# SilentStepStick_v10.net
KiCad netlist of a schematic drawn in EAGLE
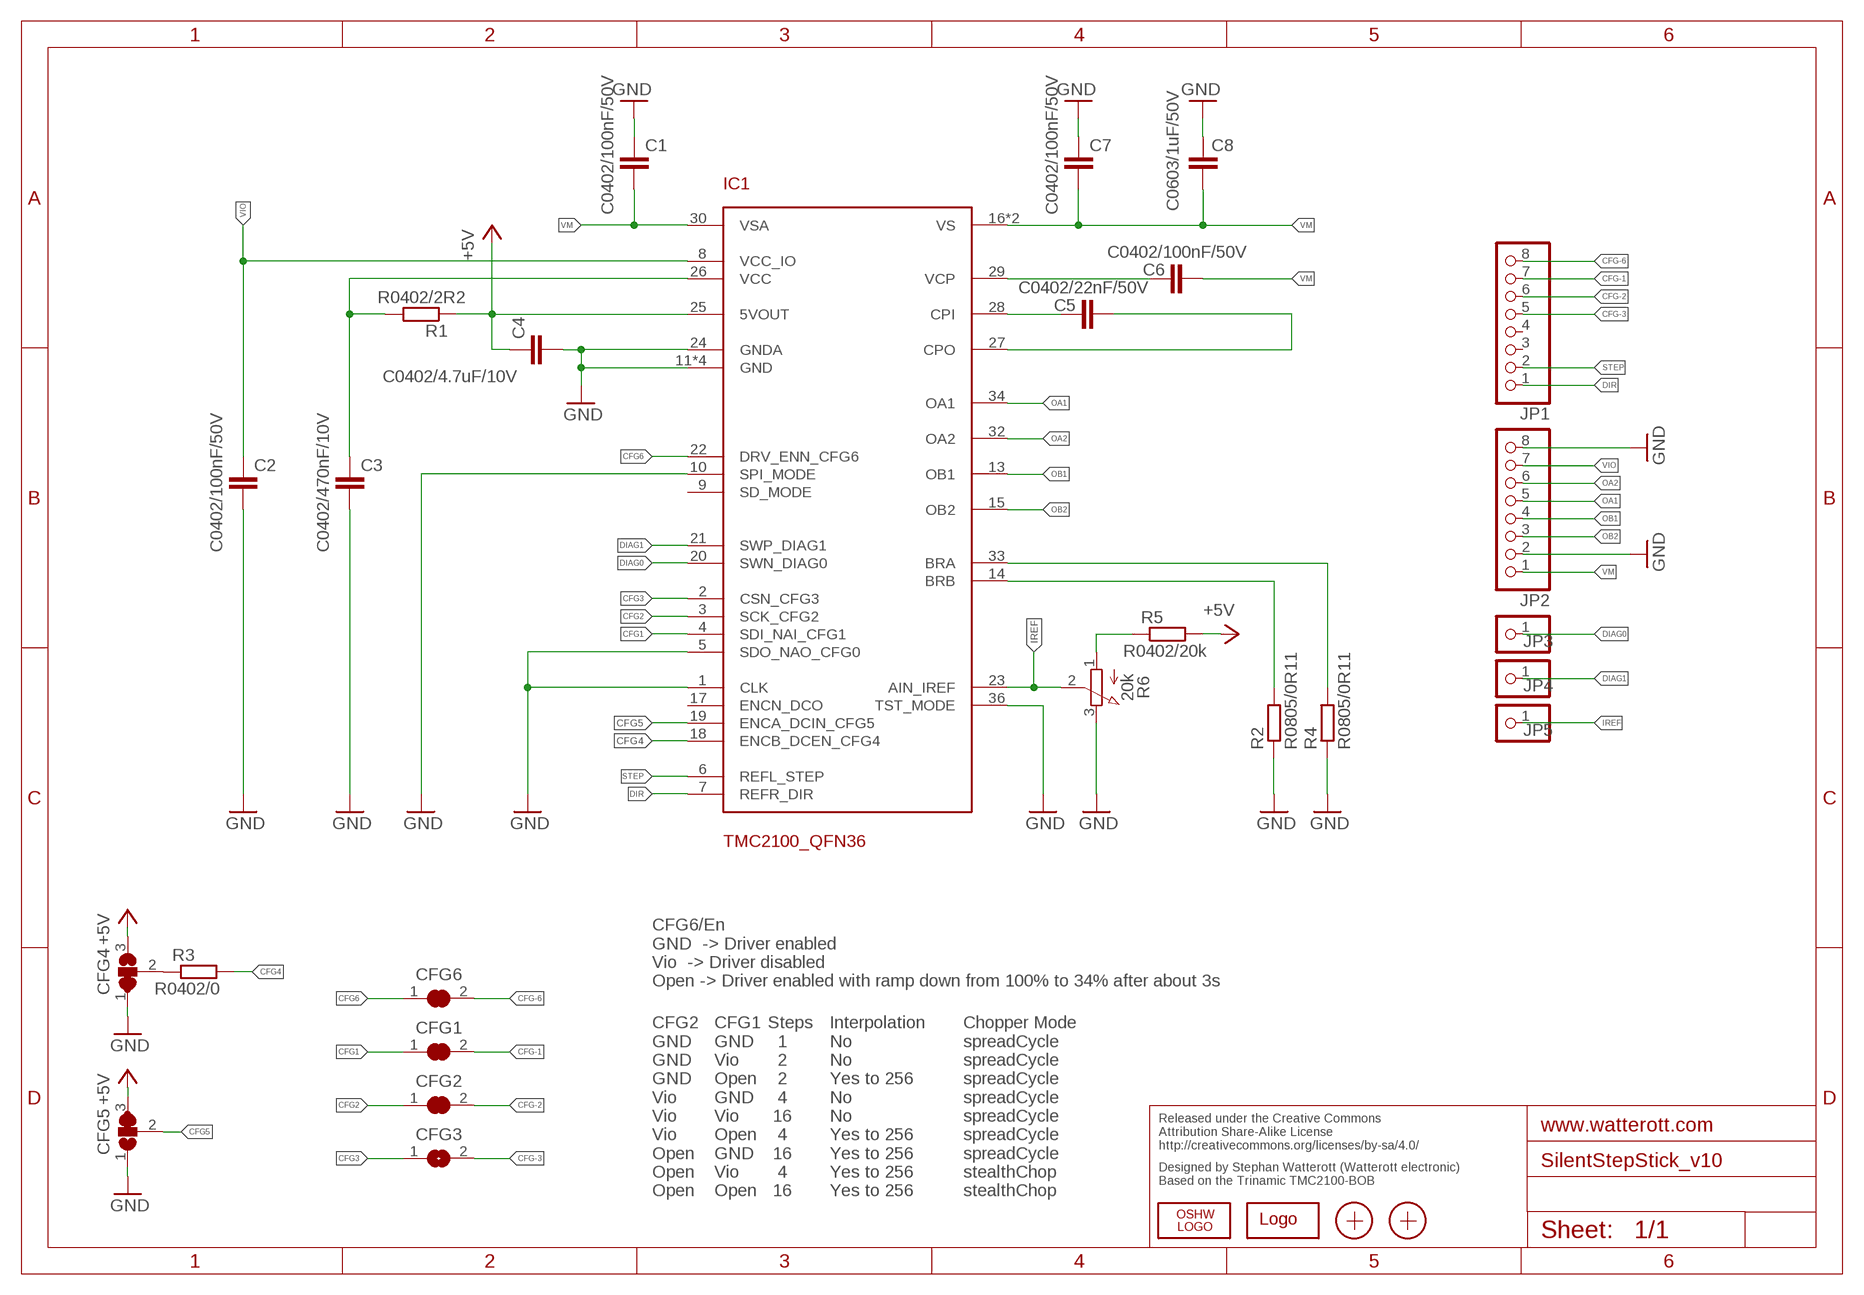
[diagram p0: schematic, sheet 1]

(export (version "E")
  (design (tool "Eeschema 10.0.6"))
  (components
    (comp (ref "C1")
      (value "C0402/100nF/50V")
      (footprint "eagle-import:C0402")
      (libsource (lib "eagle-import") (part "C-EUC0402"))
    )
    (comp (ref "C2")
      (value "C0402/100nF/50V")
      (footprint "eagle-import:C0402")
      (libsource (lib "eagle-import") (part "C-EUC0402"))
    )
    (comp (ref "C3")
      (value "C0402/470nF/10V")
      (footprint "eagle-import:C0402")
      (libsource (lib "eagle-import") (part "C-EUC0402"))
    )
    (comp (ref "C4")
      (value "C0402/4.7uF/10V")
      (footprint "eagle-import:C0402")
      (libsource (lib "eagle-import") (part "C-EUC0402"))
    )
    (comp (ref "C5")
      (value "C0402/22nF/50V")
      (footprint "eagle-import:C0402")
      (libsource (lib "eagle-import") (part "C-EUC0402"))
    )
    (comp (ref "C6")
      (value "C0402/100nF/50V")
      (footprint "eagle-import:C0402")
      (libsource (lib "eagle-import") (part "C-EUC0402"))
    )
    (comp (ref "C7")
      (value "C0402/100nF/50V")
      (footprint "eagle-import:C0402")
      (libsource (lib "eagle-import") (part "C-EUC0402"))
    )
    (comp (ref "C8")
      (value "C0603/1uF/50V")
      (footprint "eagle-import:C0603")
      (libsource (lib "eagle-import") (part "C-EUC0603"))
    )
    (comp (ref "CFG1")
      (value "JUMPER2-0201")
      (footprint "eagle-import:JUMPER2-0201")
      (libsource (lib "eagle-import") (part "JUMPER2-0201"))
    )
    (comp (ref "CFG2")
      (value "JUMPER2-0201")
      (footprint "eagle-import:JUMPER2-0201")
      (libsource (lib "eagle-import") (part "JUMPER2-0201"))
    )
    (comp (ref "CFG3")
      (value "JUMPER2-0201")
      (footprint "eagle-import:JUMPER2-0201")
      (libsource (lib "eagle-import") (part "JUMPER2-0201"))
    )
    (comp (ref "CFG4")
      (value "JUMPER3-0201-NC")
      (footprint "eagle-import:JUMPER3-0201_NC")
      (libsource (lib "eagle-import") (part "JUMPER3-0201-NC"))
    )
    (comp (ref "CFG5")
      (value "JUMPER3-0201")
      (footprint "eagle-import:JUMPER3-0201")
      (libsource (lib "eagle-import") (part "JUMPER3-0201"))
    )
    (comp (ref "CFG6")
      (value "JUMPER2-0201")
      (footprint "eagle-import:JUMPER2-0201")
      (libsource (lib "eagle-import") (part "JUMPER2-0201"))
    )
    (comp (ref "IC1")
      (value "TMC2100_QFN36")
      (footprint "eagle-import:QFN36")
      (libsource (lib "eagle-import") (part "TMC2100_QFN36"))
    )
    (comp (ref "JP1")
      (value "PINHD-1X08_2.54-S")
      (footprint "eagle-import:1X08-S")
      (libsource (lib "eagle-import") (part "PINHD-1X08_2.54-S"))
    )
    (comp (ref "JP2")
      (value "PINHD-1X08_2.54-S")
      (footprint "eagle-import:1X08-S")
      (libsource (lib "eagle-import") (part "PINHD-1X08_2.54-S"))
    )
    (comp (ref "JP3")
      (value "PINHD-1X1")
      (footprint "eagle-import:1X01")
      (libsource (lib "eagle-import") (part "PINHD-1X1"))
    )
    (comp (ref "JP4")
      (value "PINHD-1X1")
      (footprint "eagle-import:1X01")
      (libsource (lib "eagle-import") (part "PINHD-1X1"))
    )
    (comp (ref "JP5")
      (value "PINHD-1X1")
      (footprint "eagle-import:1X01")
      (libsource (lib "eagle-import") (part "PINHD-1X1"))
    )
    (comp (ref "LOGO1")
      (value "OSHW_LOGOX0070")
      (footprint "eagle-import:OSHW_6X70")
      (libsource (lib "eagle-import") (part "OSHW_LOGOX0070"))
    )
    (comp (ref "LOGO2")
      (value "LOGO-S_PLACE_M")
      (footprint "eagle-import:SPARK_TPLACE_M")
      (libsource (lib "eagle-import") (part "LOGO-S_PLACE_M"))
    )
    (comp (ref "R1")
      (value "R0402/2R2")
      (footprint "eagle-import:R0402")
      (libsource (lib "eagle-import") (part "R-EU_R0402"))
    )
    (comp (ref "R2")
      (value "R0805/0R11")
      (footprint "eagle-import:M0805")
      (libsource (lib "eagle-import") (part "R-EU_M0805"))
    )
    (comp (ref "R3")
      (value "R0402/0")
      (footprint "eagle-import:R0402")
      (libsource (lib "eagle-import") (part "R-EU_R0402"))
    )
    (comp (ref "R4")
      (value "R0805/0R11")
      (footprint "eagle-import:M0805")
      (libsource (lib "eagle-import") (part "R-EU_M0805"))
    )
    (comp (ref "R5")
      (value "R0402/20k")
      (footprint "eagle-import:R0402")
      (libsource (lib "eagle-import") (part "R-EU_R0402"))
    )
    (comp (ref "R6")
      (value "20k")
      (footprint "eagle-import:POT_EVM3R")
      (libsource (lib "eagle-import") (part "POTEVM3R"))
    )
    (comp (ref "X1")
      (value "PASSER-07")
      (footprint "eagle-import:PASSER_07MM")
      (libsource (lib "eagle-import") (part "PASSER-07"))
    )
    (comp (ref "X2")
      (value "PASSER-07")
      (footprint "eagle-import:PASSER_07MM")
      (libsource (lib "eagle-import") (part "PASSER-07"))
    )
  )
  (nets
    (net (code "1") (name "+5V") (class "Default")
      (node (ref "C4") (pin "1") (pinfunction "1_1") (pintype "passive"))
      (node (ref "CFG4") (pin "3") (pinfunction "3_3") (pintype "passive"))
      (node (ref "CFG5") (pin "3") (pinfunction "3_3") (pintype "passive"))
      (node (ref "IC1") (pin "25") (pinfunction "5VOUT_25") (pintype "bidirectional"))
      (node (ref "R1") (pin "1") (pinfunction "1_1") (pintype "passive"))
      (node (ref "R5") (pin "2") (pinfunction "2_2") (pintype "passive"))
    )
    (net (code "2") (name "CFG-1") (class "Default")
      (node (ref "CFG1") (pin "2") (pinfunction "2_2") (pintype "passive"))
      (node (ref "JP1") (pin "7") (pinfunction "7_7") (pintype "passive"))
    )
    (net (code "3") (name "CFG-2") (class "Default")
      (node (ref "CFG2") (pin "2") (pinfunction "2_2") (pintype "passive"))
      (node (ref "JP1") (pin "6") (pinfunction "6_6") (pintype "passive"))
    )
    (net (code "4") (name "CFG-3") (class "Default")
      (node (ref "CFG3") (pin "2") (pinfunction "2_2") (pintype "passive"))
      (node (ref "JP1") (pin "5") (pinfunction "5_5") (pintype "passive"))
    )
    (net (code "5") (name "CFG-6") (class "Default")
      (node (ref "CFG6") (pin "2") (pinfunction "2_2") (pintype "passive"))
      (node (ref "JP1") (pin "8") (pinfunction "8_8") (pintype "passive"))
    )
    (net (code "6") (name "CFG1") (class "Default")
      (node (ref "CFG1") (pin "1") (pinfunction "1_1") (pintype "passive"))
      (node (ref "IC1") (pin "4") (pinfunction "SDI_NAI_CFG1_4") (pintype "bidirectional"))
    )
    (net (code "7") (name "CFG2") (class "Default")
      (node (ref "CFG2") (pin "1") (pinfunction "1_1") (pintype "passive"))
      (node (ref "IC1") (pin "3") (pinfunction "SCK_CFG2_3") (pintype "bidirectional"))
    )
    (net (code "8") (name "CFG3") (class "Default")
      (node (ref "CFG3") (pin "1") (pinfunction "1_1") (pintype "passive"))
      (node (ref "IC1") (pin "2") (pinfunction "CSN_CFG3_2") (pintype "bidirectional"))
    )
    (net (code "9") (name "CFG4") (class "Default")
      (node (ref "IC1") (pin "18") (pinfunction "ENCB_DCEN_CFG4_18") (pintype "bidirectional"))
      (node (ref "R3") (pin "2") (pinfunction "2_2") (pintype "passive"))
    )
    (net (code "10") (name "CFG5") (class "Default")
      (node (ref "CFG5") (pin "2") (pinfunction "2_2") (pintype "passive"))
      (node (ref "IC1") (pin "19") (pinfunction "ENCA_DCIN_CFG5_19") (pintype "bidirectional"))
    )
    (net (code "11") (name "CFG6") (class "Default")
      (node (ref "CFG6") (pin "1") (pinfunction "1_1") (pintype "passive"))
      (node (ref "IC1") (pin "22") (pinfunction "DRV_ENN_CFG6_22") (pintype "bidirectional"))
    )
    (net (code "12") (name "DIAG0") (class "Default")
      (node (ref "IC1") (pin "20") (pinfunction "SWN_DIAG0_20") (pintype "bidirectional"))
      (node (ref "JP3") (pin "1") (pinfunction "1_1") (pintype "passive"))
    )
    (net (code "13") (name "DIAG1") (class "Default")
      (node (ref "IC1") (pin "21") (pinfunction "SWP_DIAG1_21") (pintype "bidirectional"))
      (node (ref "JP4") (pin "1") (pinfunction "1_1") (pintype "passive"))
    )
    (net (code "14") (name "DIR") (class "Default")
      (node (ref "IC1") (pin "7") (pinfunction "REFR_DIR_7") (pintype "bidirectional"))
      (node (ref "JP1") (pin "1") (pinfunction "1_1") (pintype "passive"))
    )
    (net (code "15") (name "GND") (class "Default")
      (node (ref "C1") (pin "1") (pinfunction "1_1") (pintype "passive"))
      (node (ref "C2") (pin "2") (pinfunction "2_2") (pintype "passive"))
      (node (ref "C3") (pin "2") (pinfunction "2_2") (pintype "passive"))
      (node (ref "C4") (pin "2") (pinfunction "2_2") (pintype "passive"))
      (node (ref "C7") (pin "1") (pinfunction "1_1") (pintype "passive"))
      (node (ref "C8") (pin "2") (pinfunction "2_2") (pintype "passive"))
      (node (ref "CFG4") (pin "1") (pinfunction "1_1") (pintype "passive"))
      (node (ref "CFG5") (pin "1") (pinfunction "1_1") (pintype "passive"))
      (node (ref "IC1") (pin "1") (pinfunction "CLK_1") (pintype "bidirectional"))
      (node (ref "IC1") (pin "10") (pinfunction "SPI_MODE_10") (pintype "bidirectional"))
      (node (ref "IC1") (pin "11") (pinfunction "GND_11") (pintype "bidirectional"))
      (node (ref "IC1") (pin "12") (pinfunction "GND_12") (pintype "bidirectional"))
      (node (ref "IC1") (pin "24") (pinfunction "GNDA_24") (pintype "bidirectional"))
      (node (ref "IC1") (pin "35") (pinfunction "GND_35") (pintype "bidirectional"))
      (node (ref "IC1") (pin "36") (pinfunction "TST_MODE_36") (pintype "bidirectional"))
      (node (ref "IC1") (pin "5") (pinfunction "SDO_NAO_CFG0_5") (pintype "bidirectional"))
      (node (ref "IC1") (pin "GND_PAD") (pinfunction "GND_GND_PAD") (pintype "bidirectional"))
      (node (ref "JP2") (pin "2") (pinfunction "2_2") (pintype "passive"))
      (node (ref "JP2") (pin "8") (pinfunction "8_8") (pintype "passive"))
      (node (ref "R2") (pin "1") (pinfunction "1_1") (pintype "passive"))
      (node (ref "R4") (pin "1") (pinfunction "1_1") (pintype "passive"))
      (node (ref "R6") (pin "3") (pinfunction "E_3") (pintype "passive"))
    )
    (net (code "16") (name "IREF") (class "Default")
      (node (ref "IC1") (pin "23") (pinfunction "AIN_IREF_23") (pintype "bidirectional"))
      (node (ref "JP5") (pin "1") (pinfunction "1_1") (pintype "passive"))
      (node (ref "R6") (pin "2") (pinfunction "S_2") (pintype "passive"))
    )
    (net (code "17") (name "Net-(CFG4-Pad2)") (class "Default")
      (node (ref "CFG4") (pin "2") (pinfunction "2_2") (pintype "passive"))
      (node (ref "R3") (pin "1") (pinfunction "1_1") (pintype "passive"))
    )
    (net (code "18") (name "Net-(IC1-BRA)") (class "Default")
      (node (ref "IC1") (pin "33") (pinfunction "BRA_33") (pintype "bidirectional"))
      (node (ref "R4") (pin "2") (pinfunction "2_2") (pintype "passive"))
    )
    (net (code "19") (name "Net-(IC1-BRB)") (class "Default")
      (node (ref "IC1") (pin "14") (pinfunction "BRB_14") (pintype "bidirectional"))
      (node (ref "R2") (pin "2") (pinfunction "2_2") (pintype "passive"))
    )
    (net (code "20") (name "Net-(IC1-CPI)") (class "Default")
      (node (ref "C5") (pin "1") (pinfunction "1_1") (pintype "passive"))
      (node (ref "IC1") (pin "28") (pinfunction "CPI_28") (pintype "bidirectional"))
    )
    (net (code "21") (name "Net-(IC1-CPO)") (class "Default")
      (node (ref "C5") (pin "2") (pinfunction "2_2") (pintype "passive"))
      (node (ref "IC1") (pin "27") (pinfunction "CPO_27") (pintype "bidirectional"))
    )
    (net (code "22") (name "Net-(IC1-VCC)") (class "Default")
      (node (ref "C3") (pin "1") (pinfunction "1_1") (pintype "passive"))
      (node (ref "IC1") (pin "26") (pinfunction "VCC_26") (pintype "bidirectional"))
      (node (ref "R1") (pin "2") (pinfunction "2_2") (pintype "passive"))
    )
    (net (code "23") (name "Net-(IC1-VCP)") (class "Default")
      (node (ref "C6") (pin "1") (pinfunction "1_1") (pintype "passive"))
      (node (ref "IC1") (pin "29") (pinfunction "VCP_29") (pintype "bidirectional"))
    )
    (net (code "24") (name "Net-(R6-A)") (class "Default")
      (node (ref "R5") (pin "1") (pinfunction "1_1") (pintype "passive"))
      (node (ref "R6") (pin "1") (pinfunction "A_1") (pintype "passive"))
    )
    (net (code "25") (name "OA1") (class "Default")
      (node (ref "IC1") (pin "34") (pinfunction "OA1_34") (pintype "bidirectional"))
      (node (ref "JP2") (pin "5") (pinfunction "5_5") (pintype "passive"))
    )
    (net (code "26") (name "OA2") (class "Default")
      (node (ref "IC1") (pin "32") (pinfunction "OA2_32") (pintype "bidirectional"))
      (node (ref "JP2") (pin "6") (pinfunction "6_6") (pintype "passive"))
    )
    (net (code "27") (name "OB1") (class "Default")
      (node (ref "IC1") (pin "13") (pinfunction "OB1_13") (pintype "bidirectional"))
      (node (ref "JP2") (pin "4") (pinfunction "4_4") (pintype "passive"))
    )
    (net (code "28") (name "OB2") (class "Default")
      (node (ref "IC1") (pin "15") (pinfunction "OB2_15") (pintype "bidirectional"))
      (node (ref "JP2") (pin "3") (pinfunction "3_3") (pintype "passive"))
    )
    (net (code "29") (name "STEP") (class "Default")
      (node (ref "IC1") (pin "6") (pinfunction "REFL_STEP_6") (pintype "bidirectional"))
      (node (ref "JP1") (pin "2") (pinfunction "2_2") (pintype "passive"))
    )
    (net (code "30") (name "VIO") (class "Default")
      (node (ref "C2") (pin "1") (pinfunction "1_1") (pintype "passive"))
      (node (ref "IC1") (pin "8") (pinfunction "VCC_IO_8") (pintype "bidirectional"))
      (node (ref "JP2") (pin "7") (pinfunction "7_7") (pintype "passive"))
    )
    (net (code "31") (name "VM") (class "Default")
      (node (ref "C1") (pin "2") (pinfunction "2_2") (pintype "passive"))
      (node (ref "C6") (pin "2") (pinfunction "2_2") (pintype "passive"))
      (node (ref "C7") (pin "2") (pinfunction "2_2") (pintype "passive"))
      (node (ref "C8") (pin "1") (pinfunction "1_1") (pintype "passive"))
      (node (ref "IC1") (pin "16") (pinfunction "VS_16") (pintype "bidirectional"))
      (node (ref "IC1") (pin "30") (pinfunction "VSA_30") (pintype "bidirectional"))
      (node (ref "IC1") (pin "31") (pinfunction "VS_31") (pintype "bidirectional"))
      (node (ref "JP2") (pin "1") (pinfunction "1_1") (pintype "passive"))
    )
    (net (code "32") (name "unconnected-(IC1-ENCN_DCO-Pad17)") (class "Default")
      (node (ref "IC1") (pin "17") (pinfunction "ENCN_DCO_17") (pintype "bidirectional"))
    )
    (net (code "33") (name "unconnected-(IC1-SD_MODE-Pad9)") (class "Default")
      (node (ref "IC1") (pin "9") (pinfunction "SD_MODE_9") (pintype "bidirectional"))
    )
    (net (code "34") (name "unconnected-(JP1-Pad3)") (class "Default")
      (node (ref "JP1") (pin "3") (pinfunction "3_3") (pintype "passive"))
    )
    (net (code "35") (name "unconnected-(JP1-Pad4)") (class "Default")
      (node (ref "JP1") (pin "4") (pinfunction "4_4") (pintype "passive"))
    )
  )
)
